# AstableMultivibrator.net
KiCad netlist of a schematic drawn in Altium Designer
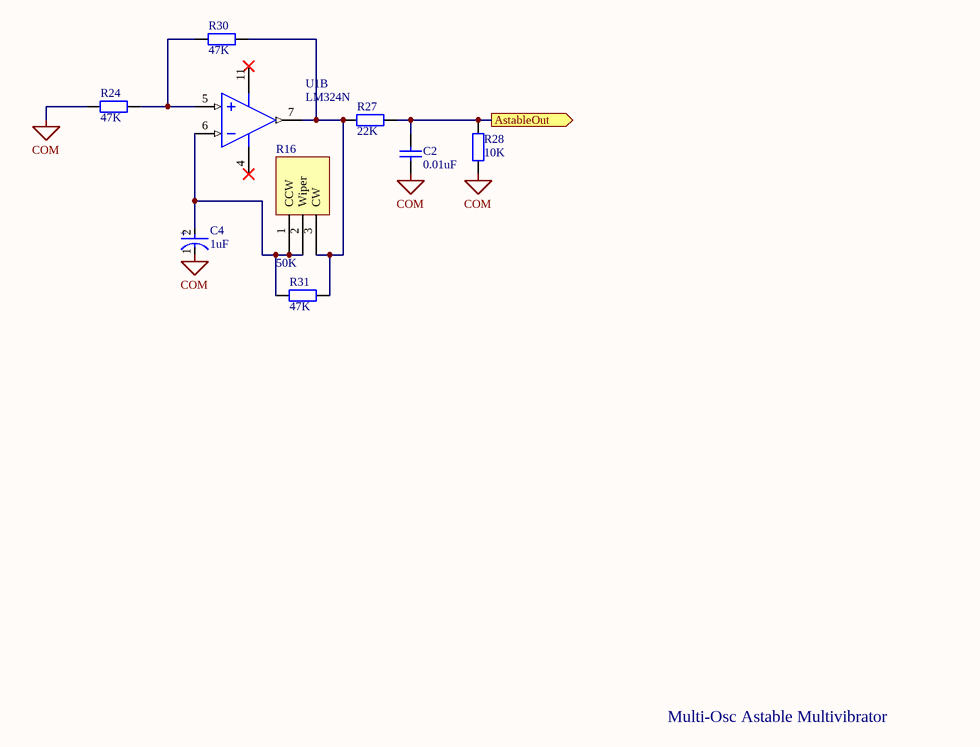
[diagram p0: AstableMultivibrator.SchDoc]

(export (version "E")
  (design (tool "Eeschema 10.0.6"))
  (components
    (comp (ref "C2")
      (value "0.01uF")
      (footprint "KEMT-C315-THT-2")
      (description "Capacitor, Ceramic, 0.01 uF, +/- 10%, 100 V, X7R, -55 to 125 degC, 2-Pin THD, RoHS, Bulk")
      (libsource (lib "Altium Content Vault") (part "CAP-NP-2"))
    )
    (comp (ref "C4")
      (value "1uF")
      (footprint "FP-ESLE3-MFG")
      (description "CAP ALUM 10UF 20% 100V THRU HOLE")
      (fields (field (name "TOLERANCE") "20%") (field (name "MANUFACTURER PART NUMBER") "ESL106M100AE3AA"))
      (libsource (lib "Altium Content Vault") (part "cf48714ba7e38822c1575c7ec0b6d1f"))
    )
    (comp (ref "R16") (value "50K") (footprint "TrimmerPot") (libsource (lib "Schlib") (part "TrimmerPot")))
    (comp (ref "R24")
      (value "47K")
      (footprint "AXIAL-0.4")
      (description "Resistor")
      (fields (field (name "PUBLISHER") "Altium Limited"))
      (libsource (lib "Miscellaneous Devices") (part "Res2"))
    )
    (comp (ref "R27")
      (value "22K")
      (footprint "AXIAL-0.4")
      (description "Resistor")
      (fields (field (name "PUBLISHER") "Altium Limited"))
      (libsource (lib "Miscellaneous Devices") (part "Res2"))
    )
    (comp (ref "R28")
      (value "10K")
      (footprint "AXIAL-0.4")
      (description "Resistor")
      (fields (field (name "PUBLISHER") "Altium Limited"))
      (libsource (lib "") (part "Res2_2"))
    )
    (comp (ref "R30")
      (value "47K")
      (footprint "AXIAL-0.4")
      (description "Resistor")
      (fields (field (name "PUBLISHER") "Altium Limited"))
      (libsource (lib "") (part "Res2_1"))
    )
    (comp (ref "R31")
      (value "47K")
      (footprint "AXIAL-0.4")
      (description "Resistor")
      (fields (field (name "PUBLISHER") "Altium Limited"))
      (libsource (lib "") (part "Res2_1"))
    )
    (comp (ref "U1")
      (value "LM324N")
      (footprint "N0014A")
      (description "Low Power Quad Operational Amplifier, 14-pin MDIP")
      (fields (field (name "MANUFACTURER") "Texas Instruments"))
      (libsource (lib "Altium Content Vault") (part "AMP-OPA-LM124-14"))
    )
  )
  (nets
    (net (code "1") (name "/AstableOut") (class "Default")
      (node (ref "C2") (pin "1") (pinfunction "1_1") (pintype "passive"))
      (node (ref "R27") (pin "2") (pinfunction "2_2") (pintype "passive"))
      (node (ref "R28") (pin "1") (pinfunction "1_1") (pintype "passive"))
    )
    (net (code "2") (name "COM") (class "Default")
      (node (ref "C2") (pin "2") (pinfunction "2_2") (pintype "passive"))
      (node (ref "C4") (pin "1") (pinfunction "C_1") (pintype "passive"))
      (node (ref "R24") (pin "1") (pinfunction "1_1") (pintype "passive"))
      (node (ref "R28") (pin "2") (pinfunction "2_2") (pintype "passive"))
    )
    (net (code "3") (name "Net-(C4-A)") (class "Default")
      (node (ref "C4") (pin "2") (pinfunction "A_2") (pintype "passive"))
      (node (ref "R16") (pin "1") (pinfunction "CCW_1") (pintype "passive"))
      (node (ref "R16") (pin "2") (pinfunction "Wiper_2") (pintype "passive"))
      (node (ref "R31") (pin "2") (pinfunction "2_2") (pintype "passive"))
      (node (ref "U1") (pin "6") (pinfunction "IN2-_6") (pintype "input"))
    )
    (net (code "4") (name "Net-(R16-CW)") (class "Default")
      (node (ref "R16") (pin "3") (pinfunction "CW_3") (pintype "passive"))
      (node (ref "R27") (pin "1") (pinfunction "1_1") (pintype "passive"))
      (node (ref "R30") (pin "1") (pinfunction "1_1") (pintype "passive"))
      (node (ref "R31") (pin "1") (pinfunction "1_1") (pintype "passive"))
      (node (ref "U1") (pin "7") (pinfunction "OUT2_7") (pintype "output"))
    )
    (net (code "5") (name "Net-(U1B-IN2+)") (class "Default")
      (node (ref "R24") (pin "2") (pinfunction "2_2") (pintype "passive"))
      (node (ref "R30") (pin "2") (pinfunction "2_2") (pintype "passive"))
      (node (ref "U1") (pin "5") (pinfunction "IN2+_5") (pintype "input"))
    )
    (net (code "6") (name "unconnected-(U1B-GND-Pad11)") (class "Default")
      (node (ref "U1") (pin "11") (pinfunction "GND_11") (pintype "power_in+no_connect"))
    )
    (net (code "7") (name "unconnected-(U1B-V+-Pad4)") (class "Default")
      (node (ref "U1") (pin "4") (pinfunction "V+_4") (pintype "power_in+no_connect"))
    )
  )
)
